# 14-misc.net
KiCad netlist of a schematic drawn in Altium Designer
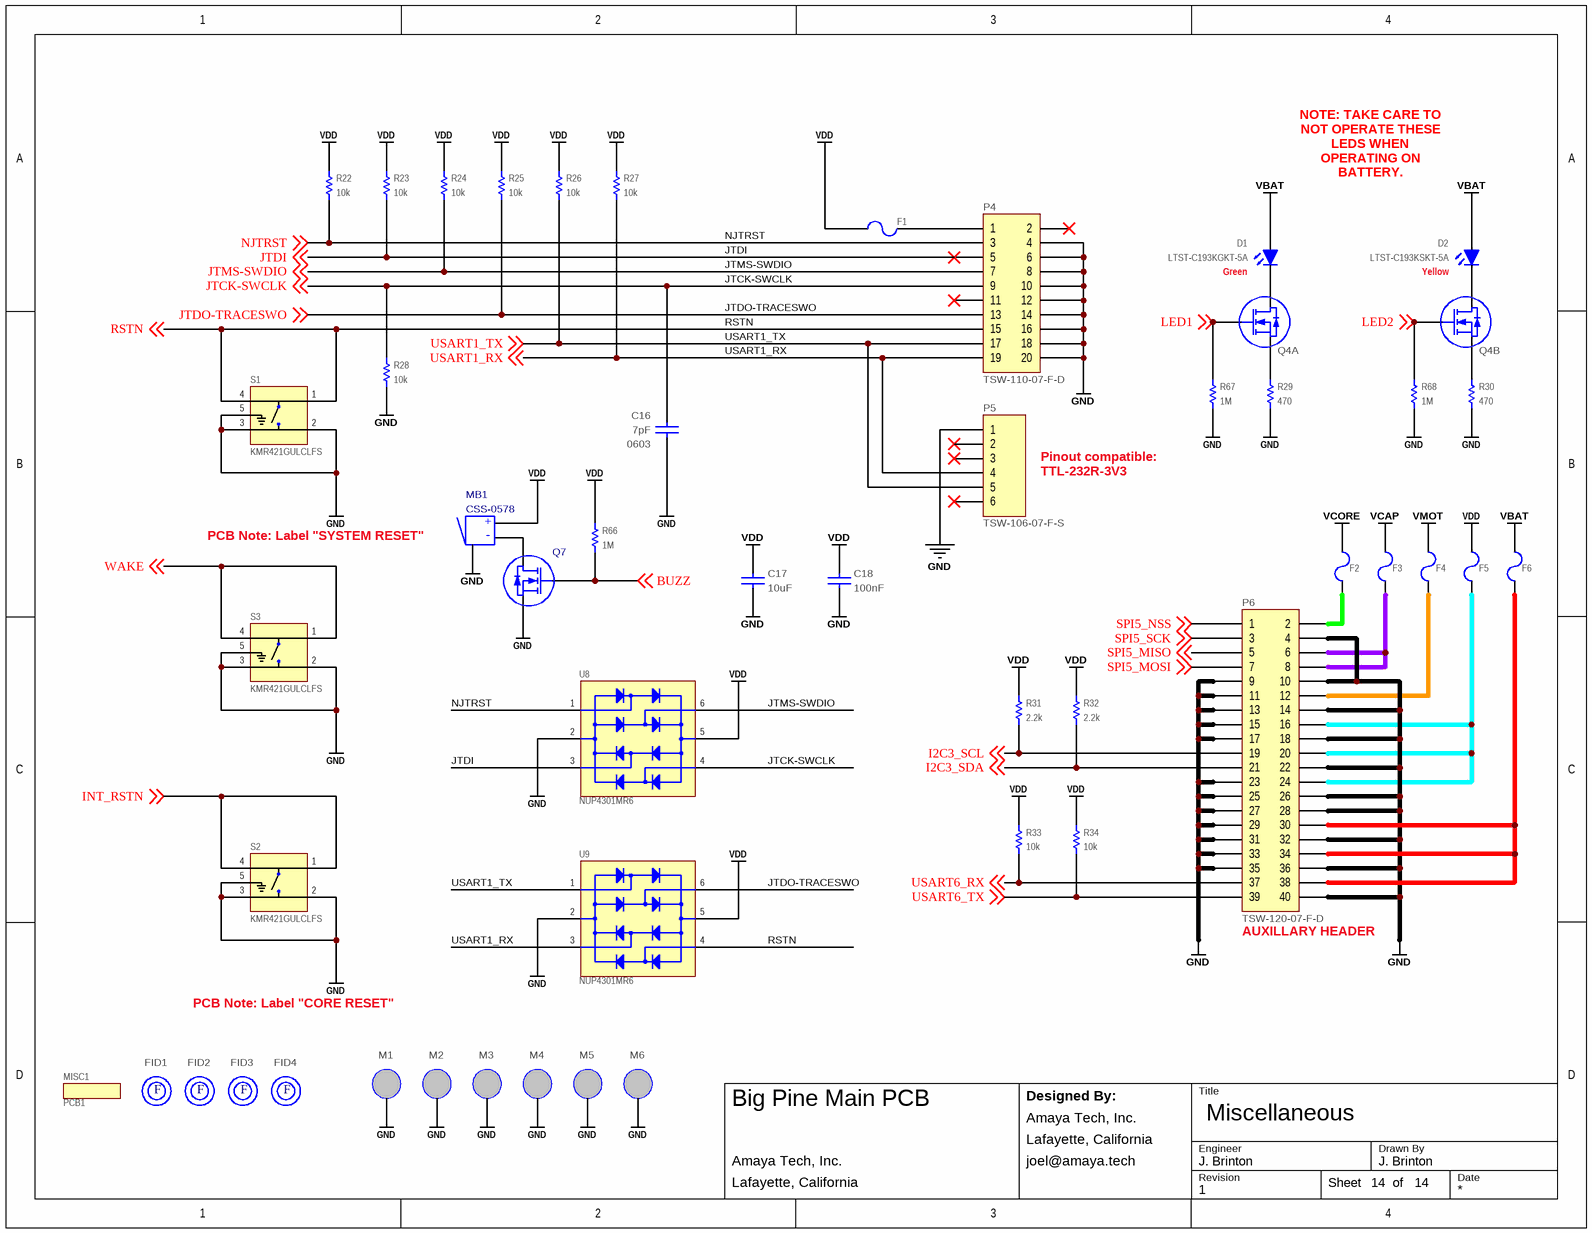
[diagram p0: 14-misc.SchDoc]

(export (version "E")
  (design (tool "Eeschema 10.0.6"))
  (components
    (comp (ref "C16")
      (value "7pF")
      (footprint "generic:CAPC160X80X90L20N")
      (description "Ceramic Capacitor 7pF +/-0.25pF 0603")
      (fields
        (field (name "MANUFACTURER") "Samsung")
        (field (name "TOLERANCE") "+/-0.25pF")
        (field (name "PACKAGE") "0603")
      )
      (libsource (lib "vishay") (part "CAP"))
    )
    (comp (ref "C17")
      (value "10uF")
      (footprint "CAPC200X125X145L45N")
      (description "Ceramic Capacitor 10uF ±10% 16V X7R 0805")
      (fields (field (name "MANUFACTURER") "Samsung") (field (name "TOLERANCE") "±10%"))
      (libsource (lib "capacitors") (part "CAP"))
    )
    (comp (ref "C18")
      (value "100nF")
      (footprint "CAPC200X125X145L45N")
      (description "Ceramic Capacitor 100nF ±10% 50V X7R 0805")
      (fields (field (name "MANUFACTURER") "Murata") (field (name "TOLERANCE") "±10%"))
      (libsource (lib "capacitors") (part "CAP"))
    )
    (comp (ref "D1")
      (value "LTST-C193KGKT-5A")
      (footprint "0603_LED")
      (description "LED, SMT 0603, Color Green, 5mA, 2V")
      (fields (field (name "MANUFACTURER") "Lite-On"))
      (libsource (lib "generic") (part "LED0603Y"))
    )
    (comp (ref "D2")
      (value "LTST-C193KSKT-5A")
      (footprint "0603_LED")
      (description "LED, SMT 0603, Color Yellow, 5mA, 2.9V")
      (fields (field (name "MANUFACTURER") "Panasonic"))
      (libsource (lib "generic") (part "LED0603Y"))
    )
    (comp (ref "F1")
      (value "0ZCJ0020FF2E")
      (footprint "generic:1206")
      (description "PTC Resettable Fuse, 0.2A, 30V, SMD 1206")
      (fields (field (name "MANUFACTURER") "Bell Fuse"))
      (libsource (lib "bel-fuse") (part "0ZCJ0020FF2E"))
    )
    (comp (ref "F2")
      (value "0ZCJ0020FF2E")
      (footprint "generic:1206")
      (description "PTC Resettable Fuse, 0.2A, 30V, SMD 1206")
      (fields (field (name "MANUFACTURER") "Bell Fuse"))
      (libsource (lib "bel-fuse") (part "0ZCJ0020FF2E"))
    )
    (comp (ref "F3")
      (value "0ZCJ0020FF2E")
      (footprint "generic:1206")
      (description "PTC Resettable Fuse, 0.2A, 30V, SMD 1206")
      (fields (field (name "MANUFACTURER") "Bell Fuse"))
      (libsource (lib "bel-fuse") (part "0ZCJ0020FF2E"))
    )
    (comp (ref "F4")
      (value "0ZCJ0020FF2E")
      (footprint "generic:1206")
      (description "PTC Resettable Fuse, 0.2A, 30V, SMD 1206")
      (fields (field (name "MANUFACTURER") "Bell Fuse"))
      (libsource (lib "bel-fuse") (part "0ZCJ0020FF2E"))
    )
    (comp (ref "F5")
      (value "0ZCJ0020FF2E")
      (footprint "generic:1206")
      (description "PTC Resettable Fuse, 0.2A, 30V, SMD 1206")
      (fields (field (name "MANUFACTURER") "Bell Fuse"))
      (libsource (lib "bel-fuse") (part "0ZCJ0020FF2E"))
    )
    (comp (ref "F6")
      (value "0ZCJ0020FF2E")
      (footprint "generic:1206")
      (description "PTC Resettable Fuse, 0.2A, 30V, SMD 1206")
      (fields (field (name "MANUFACTURER") "Bell Fuse"))
      (libsource (lib "bel-fuse") (part "0ZCJ0020FF2E"))
    )
    (comp (ref "FID1")
      (value "FIDUCIAL")
      (footprint "fiducial1mm")
      (libsource (lib "generic") (part "FIDUCIAL"))
    )
    (comp (ref "FID2")
      (value "FIDUCIAL")
      (footprint "fiducial1mm")
      (libsource (lib "generic") (part "FIDUCIAL"))
    )
    (comp (ref "FID3")
      (value "FIDUCIAL")
      (footprint "fiducial1mm")
      (libsource (lib "generic") (part "FIDUCIAL"))
    )
    (comp (ref "FID4")
      (value "FIDUCIAL")
      (footprint "fiducial1mm")
      (libsource (lib "generic") (part "FIDUCIAL"))
    )
    (comp (ref "M1") (value "MOUNT") (footprint "M4_MOUNT") (libsource (lib "generic") (part "MOUNT")))
    (comp (ref "M2") (value "MOUNT") (footprint "M4_MOUNT") (libsource (lib "generic") (part "MOUNT")))
    (comp (ref "M3") (value "MOUNT") (footprint "M4_MOUNT") (libsource (lib "generic") (part "MOUNT")))
    (comp (ref "M4") (value "MOUNT") (footprint "M4_MOUNT") (libsource (lib "generic") (part "MOUNT")))
    (comp (ref "M5") (value "MOUNT") (footprint "M4_MOUNT") (libsource (lib "generic") (part "MOUNT")))
    (comp (ref "M6") (value "MOUNT") (footprint "M4_MOUNT") (libsource (lib "generic") (part "MOUNT")))
    (comp (ref "MB1")
      (value "CSS-0578")
      (footprint "CSS-0578")
      (description "Magnetic Buzzer")
      (fields (field (name "MANUFACTURER") "CUI, Inc."))
      (libsource (lib "generic") (part "CSS-0578"))
    )
    (comp (ref "MISC1")
      (value "PCB1")
      (description "Printed Circuit Board")
      (fields (field (name "MANUFACTURER") "Aware"))
      (libsource (lib "generic") (part "MISC"))
    )
    (comp (ref "P4")
      (value "TSW-110-07-F-D")
      (footprint "samtec:TSW-110-07-F-D")
      (description "Header, 10-Pin, Dual row")
      (fields (field (name "MANUFACTURER") "Samtec"))
      (libsource (lib "Miscellaneous Connectors") (part "Header 10X2"))
    )
    (comp (ref "P5")
      (value "TSW-106-07-F-S")
      (footprint "samtec:TSW-106-07-F-S")
      (description "Header, 6-Pin")
      (fields (field (name "MANUFACTURER") "Samtec"))
      (libsource (lib "Miscellaneous Connectors") (part "Header 6"))
    )
    (comp (ref "P6")
      (value "TSW-120-07-F-D")
      (footprint "samtec:TSW-120-07-F-D")
      (description "Header, 20-Pin, Dual row")
      (fields (field (name "MANUFACTURER") "Samtec"))
      (libsource (lib "Miscellaneous Connectors") (part "Header 20X2"))
    )
    (comp (ref "Q4")
      (value "UM6K34NTCN")
      (footprint "SOT363")
      (description "Dual N-Channel Enhancement Mode MOSFET")
      (fields (field (name "MANUFACTURER") "Rohm"))
      (libsource (lib "diodes_inc") (part "2N7002DW-7-F"))
    )
    (comp (ref "Q7")
      (value "2N7002W-7-F")
      (footprint "SOT323")
      (description "N-Channel Enhancement Mode MOSFET")
      (fields (field (name "MANUFACTURER") "Diodes, Inc."))
      (libsource (lib "diodes_inc") (part "2N7002-7-F"))
    )
    (comp (ref "R22")
      (value "10k")
      (footprint "RESC2012X70N")
      (description "Thin Film Resistor 10k ±0.1% 0.125W 100V 0805")
      (fields (field (name "TOLERANCE") "±0.1%") (field (name "MANUFACTURER") "Panasonic"))
      (libsource (lib "generic") (part "RES"))
    )
    (comp (ref "R23")
      (value "10k")
      (footprint "RESC2012X70N")
      (description "Thin Film Resistor 10k ±0.1% 0.125W 100V 0805")
      (fields (field (name "TOLERANCE") "±0.1%") (field (name "MANUFACTURER") "Panasonic"))
      (libsource (lib "generic") (part "RES"))
    )
    (comp (ref "R24")
      (value "10k")
      (footprint "RESC2012X70N")
      (description "Thin Film Resistor 10k ±0.1% 0.125W 100V 0805")
      (fields (field (name "TOLERANCE") "±0.1%") (field (name "MANUFACTURER") "Panasonic"))
      (libsource (lib "generic") (part "RES"))
    )
    (comp (ref "R25")
      (value "10k")
      (footprint "RESC2012X70N")
      (description "Thin Film Resistor 10k ±0.1% 0.125W 100V 0805")
      (fields (field (name "TOLERANCE") "±0.1%") (field (name "MANUFACTURER") "Panasonic"))
      (libsource (lib "generic") (part "RES"))
    )
    (comp (ref "R26")
      (value "10k")
      (footprint "RESC2012X70N")
      (description "Thin Film Resistor 10k ±0.1% 0.125W 100V 0805")
      (fields (field (name "TOLERANCE") "±0.1%") (field (name "MANUFACTURER") "Panasonic"))
      (libsource (lib "generic") (part "RES"))
    )
    (comp (ref "R27")
      (value "10k")
      (footprint "RESC2012X70N")
      (description "Thin Film Resistor 10k ±0.1% 0.125W 100V 0805")
      (fields (field (name "TOLERANCE") "±0.1%") (field (name "MANUFACTURER") "Panasonic"))
      (libsource (lib "generic") (part "RES"))
    )
    (comp (ref "R28")
      (value "10k")
      (footprint "RESC2012X70N")
      (description "Thin Film Resistor 10k ±0.1% 0.125W 100V 0805")
      (fields (field (name "TOLERANCE") "±0.1%") (field (name "MANUFACTURER") "Panasonic"))
      (libsource (lib "generic") (part "RES"))
    )
    (comp (ref "R29")
      (value "470")
      (footprint "RESC2012X70N")
      (description "Thick Film Resistor 470 ±1% 0805")
      (fields (field (name "MANUFACTURER") "Panasonic") (field (name "TOLERANCE") "±1%"))
      (libsource (lib "Graviton") (part "RES 0402"))
    )
    (comp (ref "R30")
      (value "470")
      (footprint "RESC2012X70N")
      (description "Thick Film Resistor 470 ±1% 0805")
      (fields (field (name "MANUFACTURER") "Panasonic") (field (name "TOLERANCE") "±1%"))
      (libsource (lib "Graviton") (part "RES 0402"))
    )
    (comp (ref "R31")
      (value "2.2k")
      (footprint "RESC2012X70N")
      (description "Thin Film Resistor 2.2k ±0.1% 0.125W 100V 0805")
      (fields (field (name "TOLERANCE") "±0.1%") (field (name "MANUFACTURER") "Panasonic"))
      (libsource (lib "generic") (part "RES"))
    )
    (comp (ref "R32")
      (value "2.2k")
      (footprint "RESC2012X70N")
      (description "Thin Film Resistor 2.2k ±0.1% 0.125W 100V 0805")
      (fields (field (name "TOLERANCE") "±0.1%") (field (name "MANUFACTURER") "Panasonic"))
      (libsource (lib "generic") (part "RES"))
    )
    (comp (ref "R33")
      (value "10k")
      (footprint "RESC2012X70N")
      (description "Thin Film Resistor 10k ±0.1% 0.125W 100V 0805")
      (fields (field (name "TOLERANCE") "±0.1%") (field (name "MANUFACTURER") "Panasonic"))
      (libsource (lib "generic") (part "RES"))
    )
    (comp (ref "R34")
      (value "10k")
      (footprint "RESC2012X70N")
      (description "Thin Film Resistor 10k ±0.1% 0.125W 100V 0805")
      (fields (field (name "TOLERANCE") "±0.1%") (field (name "MANUFACTURER") "Panasonic"))
      (libsource (lib "generic") (part "RES"))
    )
    (comp (ref "R66")
      (value "1M")
      (footprint "RESC2012X70N")
      (description "Thick Film Resistor 1M ±1% 0805")
      (fields (field (name "MANUFACTURER") "Panasonic") (field (name "TOLERANCE") "±1%"))
      (libsource (lib "Graviton") (part "RES 0402"))
    )
    (comp (ref "R67")
      (value "1M")
      (footprint "RESC2012X70N")
      (description "Thick Film Resistor 1M ±1% 0805")
      (fields (field (name "MANUFACTURER") "Panasonic") (field (name "TOLERANCE") "±1%"))
      (libsource (lib "Graviton") (part "RES 0402"))
    )
    (comp (ref "R68")
      (value "1M")
      (footprint "RESC2012X70N")
      (description "Thick Film Resistor 1M ±1% 0805")
      (fields (field (name "MANUFACTURER") "Panasonic") (field (name "TOLERANCE") "±1%"))
      (libsource (lib "Graviton") (part "RES 0402"))
    )
    (comp (ref "S1")
      (value "KMR421GULCLFS")
      (footprint "SW_KMR421GULCLFS")
      (description "Switch Tactile N.O. SPST Round Button Gull Wing 0.05A 32VDC 1VA")
      (fields (field (name "MANUFACTURER") "C&K Components"))
      (libsource (lib "c&k") (part "KMR421GULCLFS"))
    )
    (comp (ref "S2")
      (value "KMR421GULCLFS")
      (footprint "SW_KMR421GULCLFS")
      (description "Switch Tactile N.O. SPST Round Button Gull Wing 0.05A 32VDC 1VA")
      (fields (field (name "MANUFACTURER") "C&K Components"))
      (libsource (lib "c&k") (part "KMR421GULCLFS"))
    )
    (comp (ref "S3")
      (value "KMR421GULCLFS")
      (footprint "SW_KMR421GULCLFS")
      (description "Switch Tactile N.O. SPST Round Button Gull Wing 0.05A 32VDC 1VA")
      (fields (field (name "MANUFACTURER") "C&K Components"))
      (libsource (lib "c&k") (part "KMR421GULCLFS"))
    )
    (comp (ref "U8")
      (value "NUP4301MR6")
      (footprint "generic:SOT23-6")
      (description "4-Lane TVS Diode Array")
      (fields (field (name "MANUFACTURER") "On Semiconductor"))
      (libsource (lib "on_semi") (part "NUP4301MR6"))
    )
    (comp (ref "U9")
      (value "NUP4301MR6")
      (footprint "generic:SOT23-6")
      (description "4-Lane TVS Diode Array")
      (fields (field (name "MANUFACTURER") "On Semiconductor"))
      (libsource (lib "on_semi") (part "NUP4301MR6"))
    )
  )
  (nets
    (net (code "1") (name "BUZZ") (class "Default")
      (node (ref "Q7") (pin "1") (pinfunction "G_1") (pintype "passive"))
      (node (ref "R66") (pin "1") (pinfunction "1_1") (pintype "passive"))
    )
    (net (code "2") (name "GND") (class "Default")
      (node (ref "C16") (pin "1") (pinfunction "1_1") (pintype "passive"))
      (node (ref "C17") (pin "2") (pinfunction "2_2") (pintype "passive"))
      (node (ref "C18") (pin "2") (pinfunction "2_2") (pintype "passive"))
      (node (ref "M1") (pin "1") (pinfunction "MNT_1") (pintype "passive"))
      (node (ref "M2") (pin "1") (pinfunction "MNT_1") (pintype "passive"))
      (node (ref "M3") (pin "1") (pinfunction "MNT_1") (pintype "passive"))
      (node (ref "M4") (pin "1") (pinfunction "MNT_1") (pintype "passive"))
      (node (ref "M5") (pin "1") (pinfunction "MNT_1") (pintype "passive"))
      (node (ref "M6") (pin "1") (pinfunction "MNT_1") (pintype "passive"))
      (node (ref "MB1") (pin "3") (pinfunction "TAB_3") (pintype "passive"))
      (node (ref "P4") (pin "10") (pinfunction "10_10") (pintype "passive"))
      (node (ref "P4") (pin "12") (pinfunction "12_12") (pintype "passive"))
      (node (ref "P4") (pin "14") (pinfunction "14_14") (pintype "passive"))
      (node (ref "P4") (pin "16") (pinfunction "16_16") (pintype "passive"))
      (node (ref "P4") (pin "18") (pinfunction "18_18") (pintype "passive"))
      (node (ref "P4") (pin "20") (pinfunction "20_20") (pintype "passive"))
      (node (ref "P4") (pin "4") (pinfunction "4_4") (pintype "passive"))
      (node (ref "P4") (pin "6") (pinfunction "6_6") (pintype "passive"))
      (node (ref "P4") (pin "8") (pinfunction "8_8") (pintype "passive"))
      (node (ref "P5") (pin "1") (pinfunction "1_1") (pintype "passive"))
      (node (ref "P6") (pin "10") (pinfunction "10_10") (pintype "passive"))
      (node (ref "P6") (pin "11") (pinfunction "11_11") (pintype "passive"))
      (node (ref "P6") (pin "13") (pinfunction "13_13") (pintype "passive"))
      (node (ref "P6") (pin "14") (pinfunction "14_14") (pintype "passive"))
      (node (ref "P6") (pin "15") (pinfunction "15_15") (pintype "passive"))
      (node (ref "P6") (pin "17") (pinfunction "17_17") (pintype "passive"))
      (node (ref "P6") (pin "18") (pinfunction "18_18") (pintype "passive"))
      (node (ref "P6") (pin "22") (pinfunction "22_22") (pintype "passive"))
      (node (ref "P6") (pin "23") (pinfunction "23_23") (pintype "passive"))
      (node (ref "P6") (pin "25") (pinfunction "25_25") (pintype "passive"))
      (node (ref "P6") (pin "26") (pinfunction "26_26") (pintype "passive"))
      (node (ref "P6") (pin "27") (pinfunction "27_27") (pintype "passive"))
      (node (ref "P6") (pin "28") (pinfunction "28_28") (pintype "passive"))
      (node (ref "P6") (pin "29") (pinfunction "29_29") (pintype "passive"))
      (node (ref "P6") (pin "31") (pinfunction "31_31") (pintype "passive"))
      (node (ref "P6") (pin "32") (pinfunction "32_32") (pintype "passive"))
      (node (ref "P6") (pin "33") (pinfunction "33_33") (pintype "passive"))
      (node (ref "P6") (pin "35") (pinfunction "35_35") (pintype "passive"))
      (node (ref "P6") (pin "36") (pinfunction "36_36") (pintype "passive"))
      (node (ref "P6") (pin "4") (pinfunction "4_4") (pintype "passive"))
      (node (ref "P6") (pin "40") (pinfunction "40_40") (pintype "passive"))
      (node (ref "P6") (pin "9") (pinfunction "9_9") (pintype "passive"))
      (node (ref "Q7") (pin "2") (pinfunction "S_2") (pintype "passive"))
      (node (ref "R28") (pin "1") (pinfunction "1_1") (pintype "passive"))
      (node (ref "R29") (pin "1") (pinfunction "1_1") (pintype "passive"))
      (node (ref "R30") (pin "1") (pinfunction "1_1") (pintype "passive"))
      (node (ref "R67") (pin "1") (pinfunction "1_1") (pintype "passive"))
      (node (ref "R68") (pin "1") (pinfunction "1_1") (pintype "passive"))
      (node (ref "S1") (pin "2") (pinfunction "2_2") (pintype "passive"))
      (node (ref "S1") (pin "3") (pinfunction "3_3") (pintype "passive"))
      (node (ref "S1") (pin "5") (pinfunction "G_5") (pintype "power_in"))
      (node (ref "S2") (pin "2") (pinfunction "2_2") (pintype "passive"))
      (node (ref "S2") (pin "3") (pinfunction "3_3") (pintype "passive"))
      (node (ref "S2") (pin "5") (pinfunction "G_5") (pintype "power_in"))
      (node (ref "S3") (pin "2") (pinfunction "2_2") (pintype "passive"))
      (node (ref "S3") (pin "3") (pinfunction "3_3") (pintype "passive"))
      (node (ref "S3") (pin "5") (pinfunction "G_5") (pintype "power_in"))
      (node (ref "U8") (pin "2") (pinfunction "VN_2") (pintype "passive"))
      (node (ref "U9") (pin "2") (pinfunction "VN_2") (pintype "passive"))
    )
    (net (code "3") (name "I2C3_SCL") (class "Default")
      (node (ref "P6") (pin "19") (pinfunction "19_19") (pintype "passive"))
      (node (ref "R31") (pin "1") (pinfunction "1_1") (pintype "passive"))
    )
    (net (code "4") (name "I2C3_SDA") (class "Default")
      (node (ref "P6") (pin "21") (pinfunction "21_21") (pintype "passive"))
      (node (ref "R32") (pin "1") (pinfunction "1_1") (pintype "passive"))
    )
    (net (code "5") (name "INT_RSTN") (class "Default")
      (node (ref "S2") (pin "1") (pinfunction "1_1") (pintype "passive"))
      (node (ref "S2") (pin "4") (pinfunction "4_4") (pintype "passive"))
    )
    (net (code "6") (name "JTCK-SWCLK") (class "Default")
      (node (ref "C16") (pin "2") (pinfunction "2_2") (pintype "passive"))
      (node (ref "P4") (pin "9") (pinfunction "9_9") (pintype "passive"))
      (node (ref "R28") (pin "2") (pinfunction "2_2") (pintype "passive"))
      (node (ref "U8") (pin "4") (pinfunction "C_4") (pintype "passive"))
    )
    (net (code "7") (name "JTDI") (class "Default")
      (node (ref "P4") (pin "5") (pinfunction "5_5") (pintype "passive"))
      (node (ref "R23") (pin "1") (pinfunction "1_1") (pintype "passive"))
      (node (ref "U8") (pin "3") (pinfunction "B_3") (pintype "passive"))
    )
    (net (code "8") (name "JTDO-TRACESWO") (class "Default")
      (node (ref "P4") (pin "13") (pinfunction "13_13") (pintype "passive"))
      (node (ref "R25") (pin "1") (pinfunction "1_1") (pintype "passive"))
      (node (ref "U9") (pin "6") (pinfunction "D_6") (pintype "passive"))
    )
    (net (code "9") (name "JTMS-SWDIO") (class "Default")
      (node (ref "P4") (pin "7") (pinfunction "7_7") (pintype "passive"))
      (node (ref "R24") (pin "1") (pinfunction "1_1") (pintype "passive"))
      (node (ref "U8") (pin "6") (pinfunction "D_6") (pintype "passive"))
    )
    (net (code "10") (name "LED1") (class "Default")
      (node (ref "Q4") (pin "5") (pinfunction "G1_5") (pintype "passive"))
      (node (ref "R67") (pin "2") (pinfunction "2_2") (pintype "passive"))
    )
    (net (code "11") (name "LED2") (class "Default")
      (node (ref "Q4") (pin "2") (pinfunction "G2_2") (pintype "passive"))
      (node (ref "R68") (pin "2") (pinfunction "2_2") (pintype "passive"))
    )
    (net (code "12") (name "NJTRST") (class "Default")
      (node (ref "P4") (pin "3") (pinfunction "3_3") (pintype "passive"))
      (node (ref "R22") (pin "1") (pinfunction "1_1") (pintype "passive"))
      (node (ref "U8") (pin "1") (pinfunction "A_1") (pintype "passive"))
    )
    (net (code "13") (name "Net-(D1-K)") (class "Default")
      (node (ref "D1") (pin "2") (pinfunction "K_2") (pintype "passive"))
      (node (ref "Q4") (pin "3") (pinfunction "D1_3") (pintype "passive"))
    )
    (net (code "14") (name "Net-(D2-K)") (class "Default")
      (node (ref "D2") (pin "2") (pinfunction "K_2") (pintype "passive"))
      (node (ref "Q4") (pin "6") (pinfunction "D2_6") (pintype "passive"))
    )
    (net (code "15") (name "Net-(F1-Pad2)") (class "Default")
      (node (ref "F1") (pin "2") (pinfunction "2_2") (pintype "passive"))
      (node (ref "P4") (pin "1") (pinfunction "1_1") (pintype "passive"))
    )
    (net (code "16") (name "Net-(F2-Pad2)") (class "Default")
      (node (ref "F2") (pin "2") (pinfunction "2_2") (pintype "passive"))
      (node (ref "P6") (pin "2") (pinfunction "2_2") (pintype "passive"))
    )
    (net (code "17") (name "Net-(F3-Pad2)") (class "Default")
      (node (ref "F3") (pin "2") (pinfunction "2_2") (pintype "passive"))
      (node (ref "P6") (pin "6") (pinfunction "6_6") (pintype "passive"))
      (node (ref "P6") (pin "8") (pinfunction "8_8") (pintype "passive"))
    )
    (net (code "18") (name "Net-(F4-Pad2)") (class "Default")
      (node (ref "F4") (pin "2") (pinfunction "2_2") (pintype "passive"))
      (node (ref "P6") (pin "12") (pinfunction "12_12") (pintype "passive"))
    )
    (net (code "19") (name "Net-(F5-Pad2)") (class "Default")
      (node (ref "F5") (pin "2") (pinfunction "2_2") (pintype "passive"))
      (node (ref "P6") (pin "16") (pinfunction "16_16") (pintype "passive"))
      (node (ref "P6") (pin "20") (pinfunction "20_20") (pintype "passive"))
      (node (ref "P6") (pin "24") (pinfunction "24_24") (pintype "passive"))
    )
    (net (code "20") (name "Net-(F6-Pad2)") (class "Default")
      (node (ref "F6") (pin "2") (pinfunction "2_2") (pintype "passive"))
      (node (ref "P6") (pin "30") (pinfunction "30_30") (pintype "passive"))
      (node (ref "P6") (pin "34") (pinfunction "34_34") (pintype "passive"))
      (node (ref "P6") (pin "38") (pinfunction "38_38") (pintype "passive"))
    )
    (net (code "21") (name "Net-(MB1-NEG)") (class "Default")
      (node (ref "MB1") (pin "2") (pinfunction "NEG_2") (pintype "passive"))
      (node (ref "Q7") (pin "3") (pinfunction "D_3") (pintype "passive"))
    )
    (net (code "22") (name "Net-(Q4A-S1)") (class "Default")
      (node (ref "Q4") (pin "4") (pinfunction "S1_4") (pintype "passive"))
      (node (ref "R29") (pin "2") (pinfunction "2_2") (pintype "passive"))
    )
    (net (code "23") (name "Net-(Q4B-S2)") (class "Default")
      (node (ref "Q4") (pin "1") (pinfunction "S2_1") (pintype "passive"))
      (node (ref "R30") (pin "2") (pinfunction "2_2") (pintype "passive"))
    )
    (net (code "24") (name "RSTN") (class "Default")
      (node (ref "P4") (pin "15") (pinfunction "15_15") (pintype "passive"))
      (node (ref "S1") (pin "1") (pinfunction "1_1") (pintype "passive"))
      (node (ref "S1") (pin "4") (pinfunction "4_4") (pintype "passive"))
      (node (ref "U9") (pin "4") (pinfunction "C_4") (pintype "passive"))
    )
    (net (code "25") (name "SPI5_MISO") (class "Default")
      (node (ref "P6") (pin "5") (pinfunction "5_5") (pintype "passive"))
    )
    (net (code "26") (name "SPI5_MOSI") (class "Default")
      (node (ref "P6") (pin "7") (pinfunction "7_7") (pintype "passive"))
    )
    (net (code "27") (name "SPI5_NSS") (class "Default")
      (node (ref "P6") (pin "1") (pinfunction "1_1") (pintype "passive"))
    )
    (net (code "28") (name "SPI5_SCK") (class "Default")
      (node (ref "P6") (pin "3") (pinfunction "3_3") (pintype "passive"))
    )
    (net (code "29") (name "USART1_RX") (class "Default")
      (node (ref "P4") (pin "19") (pinfunction "19_19") (pintype "passive"))
      (node (ref "P5") (pin "4") (pinfunction "4_4") (pintype "passive"))
      (node (ref "R27") (pin "1") (pinfunction "1_1") (pintype "passive"))
      (node (ref "U9") (pin "3") (pinfunction "B_3") (pintype "passive"))
    )
    (net (code "30") (name "USART1_TX") (class "Default")
      (node (ref "P4") (pin "17") (pinfunction "17_17") (pintype "passive"))
      (node (ref "P5") (pin "5") (pinfunction "5_5") (pintype "passive"))
      (node (ref "R26") (pin "1") (pinfunction "1_1") (pintype "passive"))
      (node (ref "U9") (pin "1") (pinfunction "A_1") (pintype "passive"))
    )
    (net (code "31") (name "USART6_RX") (class "Default")
      (node (ref "P6") (pin "37") (pinfunction "37_37") (pintype "passive"))
      (node (ref "R33") (pin "1") (pinfunction "1_1") (pintype "passive"))
    )
    (net (code "32") (name "USART6_TX") (class "Default")
      (node (ref "P6") (pin "39") (pinfunction "39_39") (pintype "passive"))
      (node (ref "R34") (pin "1") (pinfunction "1_1") (pintype "passive"))
    )
    (net (code "33") (name "VBAT") (class "Default")
      (node (ref "D1") (pin "1") (pinfunction "A_1") (pintype "passive"))
      (node (ref "D2") (pin "1") (pinfunction "A_1") (pintype "passive"))
      (node (ref "F6") (pin "1") (pinfunction "1_1") (pintype "passive"))
    )
    (net (code "34") (name "VCAP") (class "Default")
      (node (ref "F3") (pin "1") (pinfunction "1_1") (pintype "passive"))
    )
    (net (code "35") (name "VCORE") (class "Default")
      (node (ref "F2") (pin "1") (pinfunction "1_1") (pintype "passive"))
    )
    (net (code "36") (name "VDD") (class "Default")
      (node (ref "C17") (pin "1") (pinfunction "1_1") (pintype "passive"))
      (node (ref "C18") (pin "1") (pinfunction "1_1") (pintype "passive"))
      (node (ref "F1") (pin "1") (pinfunction "1_1") (pintype "passive"))
      (node (ref "F5") (pin "1") (pinfunction "1_1") (pintype "passive"))
      (node (ref "MB1") (pin "1") (pinfunction "POS_1") (pintype "passive"))
      (node (ref "R22") (pin "2") (pinfunction "2_2") (pintype "passive"))
      (node (ref "R23") (pin "2") (pinfunction "2_2") (pintype "passive"))
      (node (ref "R24") (pin "2") (pinfunction "2_2") (pintype "passive"))
      (node (ref "R25") (pin "2") (pinfunction "2_2") (pintype "passive"))
      (node (ref "R26") (pin "2") (pinfunction "2_2") (pintype "passive"))
      (node (ref "R27") (pin "2") (pinfunction "2_2") (pintype "passive"))
      (node (ref "R31") (pin "2") (pinfunction "2_2") (pintype "passive"))
      (node (ref "R32") (pin "2") (pinfunction "2_2") (pintype "passive"))
      (node (ref "R33") (pin "2") (pinfunction "2_2") (pintype "passive"))
      (node (ref "R34") (pin "2") (pinfunction "2_2") (pintype "passive"))
      (node (ref "R66") (pin "2") (pinfunction "2_2") (pintype "passive"))
      (node (ref "U8") (pin "5") (pinfunction "VP_5") (pintype "passive"))
      (node (ref "U9") (pin "5") (pinfunction "VP_5") (pintype "passive"))
    )
    (net (code "37") (name "VMOT") (class "Default")
      (node (ref "F4") (pin "1") (pinfunction "1_1") (pintype "passive"))
    )
    (net (code "38") (name "WAKE") (class "Default")
      (node (ref "S3") (pin "1") (pinfunction "1_1") (pintype "passive"))
      (node (ref "S3") (pin "4") (pinfunction "4_4") (pintype "passive"))
    )
    (net (code "39") (name "unconnected-(P4-Pad2)") (class "Default")
      (node (ref "P4") (pin "2") (pinfunction "2_2") (pintype "passive+no_connect"))
    )
    (net (code "40") (name "unconnected-(P4-Pad11)") (class "Default")
      (node (ref "P4") (pin "11") (pinfunction "11_11") (pintype "passive+no_connect"))
    )
    (net (code "41") (name "unconnected-(P5-Pad2)") (class "Default")
      (node (ref "P5") (pin "2") (pinfunction "2_2") (pintype "passive+no_connect"))
    )
    (net (code "42") (name "unconnected-(P5-Pad3)") (class "Default")
      (node (ref "P5") (pin "3") (pinfunction "3_3") (pintype "passive+no_connect"))
    )
    (net (code "43") (name "unconnected-(P5-Pad6)") (class "Default")
      (node (ref "P5") (pin "6") (pinfunction "6_6") (pintype "passive+no_connect"))
    )
  )
)
